# PX4FMUv2_4_6_8.net
KiCad netlist of a schematic drawn in Altium Designer
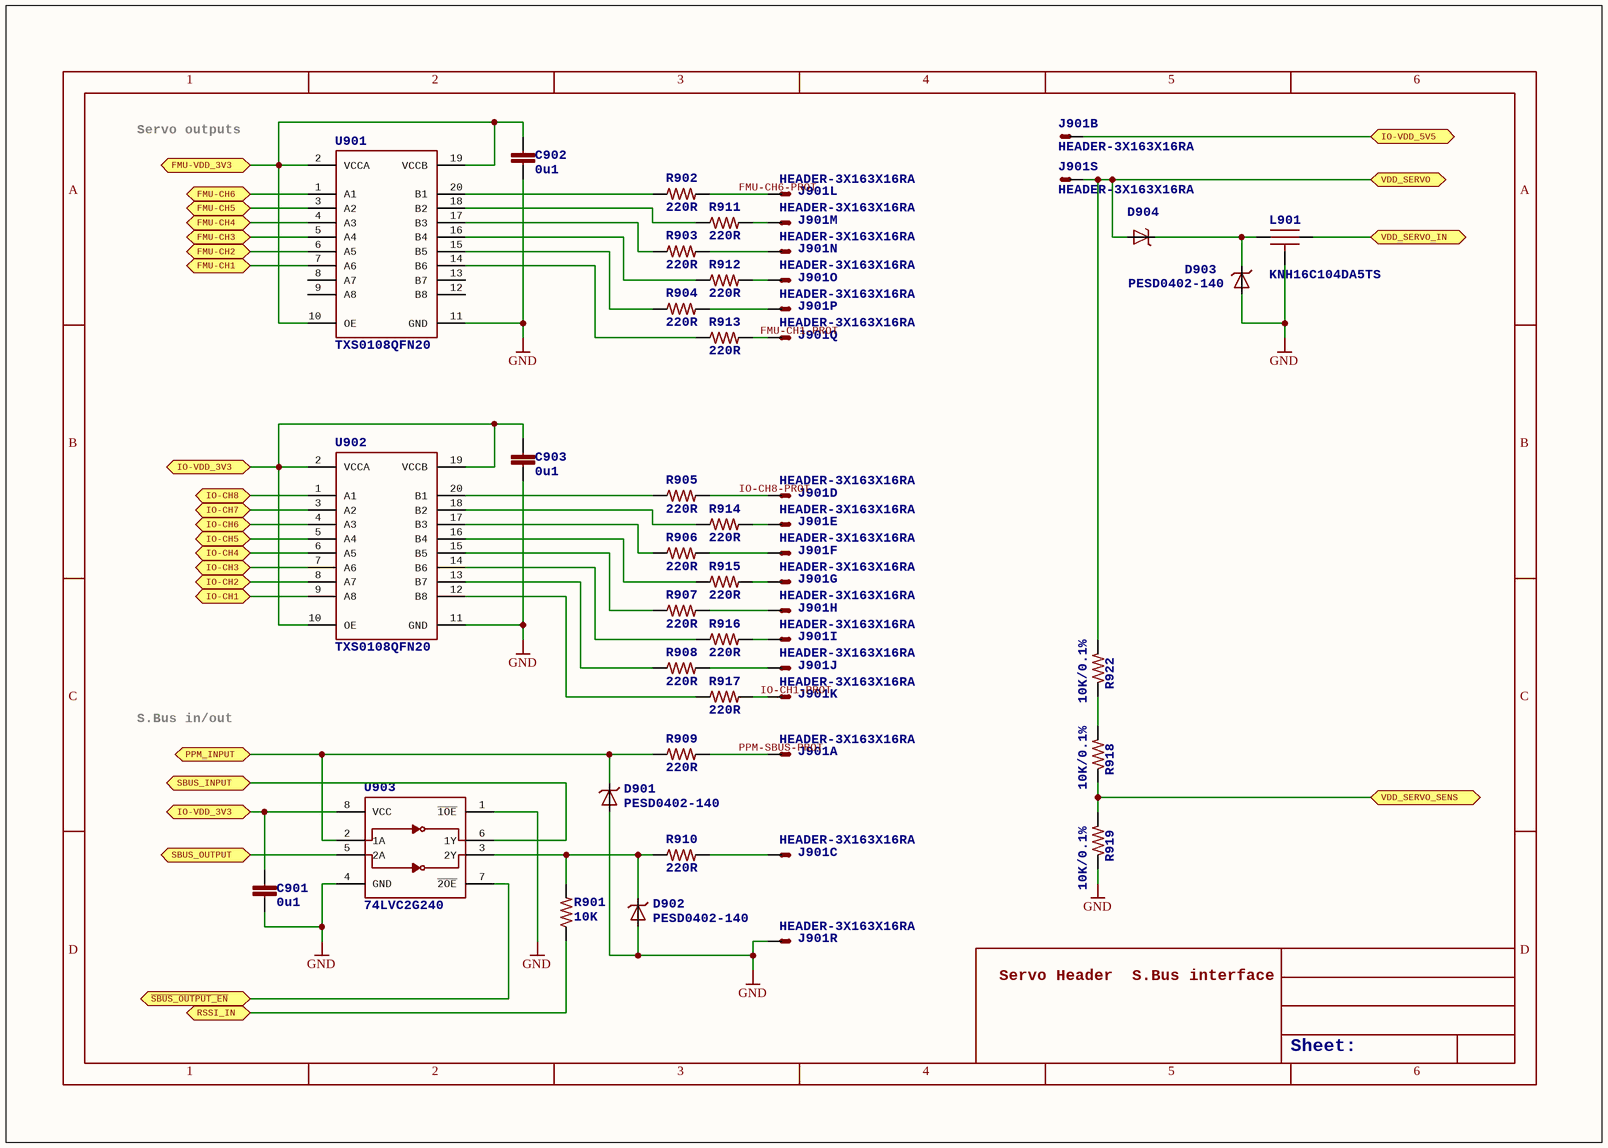
[diagram p0: PX4FMUv2.4.6_8.SchDoc]

(export (version "E")
  (design (tool "Eeschema 10.0.6"))
  (components
    (comp (ref "C901")
      (value "0u1")
      (footprint "0402-CAP")
      (description "CapacitorStandard 0603 ceramic capacitor, and 0.1\" leaded capacitor.")
      (fields (field (name "PARTNO") "CC0402ZRY5V7BB104"))
      (libsource (lib "") (part "CAP0402_1"))
    )
    (comp (ref "C902")
      (value "0u1")
      (footprint "0402-CAP")
      (description "CapacitorStandard 0603 ceramic capacitor, and 0.1\" leaded capacitor.")
      (fields (field (name "PARTNO") "CC0402ZRY5V7BB104"))
      (libsource (lib "pixhawk2") (part "CAP0402"))
    )
    (comp (ref "C903")
      (value "0u1")
      (footprint "0402-CAP")
      (description "CapacitorStandard 0603 ceramic capacitor, and 0.1\" leaded capacitor.")
      (fields (field (name "PARTNO") "CC0402ZRY5V7BB104"))
      (libsource (lib "pixhawk2") (part "CAP0402"))
    )
    (comp (ref "D901")
      (value "PESD0402-140")
      (footprint "0402-TVS")
      (libsource (lib "pixhawk2") (part "DIODE-TVS"))
    )
    (comp (ref "D902")
      (value "PESD0402-140")
      (footprint "0402-TVS")
      (libsource (lib "pixhawk2") (part "DIODE-TVS"))
    )
    (comp (ref "D903")
      (value "PESD0402-140")
      (footprint "0402-TVS")
      (libsource (lib "pixhawk2") (part "DIODE-TVS"))
    )
    (comp (ref "D904")
      (value "MSS1P4-M3")
      (footprint "MICROSMP")
      (description "Schottky barrier diode in DO214AC, e.g. Fairchild SS14.")
      (libsource (lib "pixhawk2") (part "DIODE-SCHOTTKY_MSMP"))
    )
    (comp (ref "J901")
      (value "HEADER-3X163X16RA")
      (footprint "3X16RA")
      (description "3x16 servo header")
      (libsource (lib "pixhawk2") (part "HEADER-3X163X16RA"))
    )
    (comp (ref "L901")
      (value "KNH16C104DA5TS")
      (footprint "KYOCERA-KNH16-DA")
      (description "Kyocera KNH16C104DA5TS EMI filter")
      (libsource (lib "pixhawk2") (part "KNH16C104DA5TS"))
    )
    (comp (ref "R901")
      (value "10K")
      (footprint "0402-RES")
      (fields (field (name "PARTNO") "RC0402FR-0710KL"))
      (libsource (lib "pixhawk2") (part "RESISTOR0402-RES"))
    )
    (comp (ref "R902")
      (value "220R")
      (footprint "0402-RES")
      (fields (field (name "PARTNO") "RC0402FR-07220RL"))
      (libsource (lib "pixhawk2") (part "RESISTOR0402-RES"))
    )
    (comp (ref "R903")
      (value "220R")
      (footprint "0402-RES")
      (fields (field (name "PARTNO") "RC0402FR-07220RL"))
      (libsource (lib "pixhawk2") (part "RESISTOR0402-RES"))
    )
    (comp (ref "R904")
      (value "220R")
      (footprint "0402-RES")
      (fields (field (name "PARTNO") "RC0402FR-07220RL"))
      (libsource (lib "pixhawk2") (part "RESISTOR0402-RES"))
    )
    (comp (ref "R905")
      (value "220R")
      (footprint "0402-RES")
      (fields (field (name "PARTNO") "RC0402FR-07220RL"))
      (libsource (lib "pixhawk2") (part "RESISTOR0402-RES"))
    )
    (comp (ref "R906")
      (value "220R")
      (footprint "0402-RES")
      (fields (field (name "PARTNO") "RC0402FR-07220RL"))
      (libsource (lib "pixhawk2") (part "RESISTOR0402-RES"))
    )
    (comp (ref "R907")
      (value "220R")
      (footprint "0402-RES")
      (fields (field (name "PARTNO") "RC0402FR-07220RL"))
      (libsource (lib "pixhawk2") (part "RESISTOR0402-RES"))
    )
    (comp (ref "R908")
      (value "220R")
      (footprint "0402-RES")
      (fields (field (name "PARTNO") "RC0402FR-07220RL"))
      (libsource (lib "pixhawk2") (part "RESISTOR0402-RES"))
    )
    (comp (ref "R909")
      (value "220R")
      (footprint "0402-RES")
      (fields (field (name "PARTNO") "RC0402FR-07220RL"))
      (libsource (lib "pixhawk2") (part "RESISTOR0402-RES"))
    )
    (comp (ref "R910")
      (value "220R")
      (footprint "0402-RES")
      (fields (field (name "PARTNO") "RC0402FR-07220RL"))
      (libsource (lib "pixhawk2") (part "RESISTOR0402-RES"))
    )
    (comp (ref "R911")
      (value "220R")
      (footprint "0402-RES")
      (fields (field (name "PARTNO") "RC0402FR-07220RL"))
      (libsource (lib "pixhawk2") (part "RESISTOR0402-RES"))
    )
    (comp (ref "R912")
      (value "220R")
      (footprint "0402-RES")
      (fields (field (name "PARTNO") "RC0402FR-07220RL"))
      (libsource (lib "pixhawk2") (part "RESISTOR0402-RES"))
    )
    (comp (ref "R913")
      (value "220R")
      (footprint "0402-RES")
      (fields (field (name "PARTNO") "RC0402FR-07220RL"))
      (libsource (lib "pixhawk2") (part "RESISTOR0402-RES"))
    )
    (comp (ref "R914")
      (value "220R")
      (footprint "0402-RES")
      (fields (field (name "PARTNO") "RC0402FR-07220RL"))
      (libsource (lib "pixhawk2") (part "RESISTOR0402-RES"))
    )
    (comp (ref "R915")
      (value "220R")
      (footprint "0402-RES")
      (fields (field (name "PARTNO") "RC0402FR-07220RL"))
      (libsource (lib "pixhawk2") (part "RESISTOR0402-RES"))
    )
    (comp (ref "R916")
      (value "220R")
      (footprint "0402-RES")
      (fields (field (name "PARTNO") "RC0402FR-07220RL"))
      (libsource (lib "pixhawk2") (part "RESISTOR0402-RES"))
    )
    (comp (ref "R917")
      (value "220R")
      (footprint "0402-RES")
      (fields (field (name "PARTNO") "RC0402FR-07220RL"))
      (libsource (lib "pixhawk2") (part "RESISTOR0402-RES"))
    )
    (comp (ref "R918")
      (value "10K/0.1%")
      (footprint "0402-RES")
      (libsource (lib "pixhawk2") (part "RESISTOR0402-RES"))
    )
    (comp (ref "R919")
      (value "10K/0.1%")
      (footprint "0402-RES")
      (libsource (lib "pixhawk2") (part "RESISTOR0402-RES"))
    )
    (comp (ref "R922")
      (value "10K/0.1%")
      (footprint "0402-RES")
      (libsource (lib "pixhawk2") (part "RESISTOR0402-RES"))
    )
    (comp (ref "U901")
      (value "TXS0108QFN20")
      (footprint "QFN20-RGY")
      (fields (field (name "PARTNO") "TXS0108ERGYR"))
      (libsource (lib "pixhawk2") (part "TXS0108QFN20"))
    )
    (comp (ref "U902")
      (value "TXS0108QFN20")
      (footprint "QFN20-RGY")
      (fields (field (name "PARTNO") "TXS0108ERGYR"))
      (libsource (lib "pixhawk2") (part "TXS0108QFN20"))
    )
    (comp (ref "U903")
      (value "74LVC2G240")
      (footprint "TSSOP8_SOT505-2")
      (fields (field (name "PARTNO") "74LVC2G240DP,125"))
      (libsource (lib "pixhawk2") (part "74LVC2G240-TSSOP-8"))
    )
  )
  (nets
    (net (code "1") (name "/FMU-CH1") (class "Default")
      (node (ref "U901") (pin "7") (pinfunction "A6_7") (pintype "passive"))
    )
    (net (code "2") (name "/FMU-CH1-PROT") (class "Default")
      (node (ref "J901") (pin "46") (pinfunction "S_46") (pintype "passive"))
      (node (ref "R913") (pin "P$2") (pinfunction "2_P$2") (pintype "passive"))
    )
    (net (code "3") (name "/FMU-CH2") (class "Default")
      (node (ref "U901") (pin "6") (pinfunction "A5_6") (pintype "passive"))
    )
    (net (code "4") (name "/FMU-CH3") (class "Default")
      (node (ref "U901") (pin "5") (pinfunction "A4_5") (pintype "passive"))
    )
    (net (code "5") (name "/FMU-CH4") (class "Default")
      (node (ref "U901") (pin "4") (pinfunction "A3_4") (pintype "passive"))
    )
    (net (code "6") (name "/FMU-CH5") (class "Default")
      (node (ref "U901") (pin "3") (pinfunction "A2_3") (pintype "passive"))
    )
    (net (code "7") (name "/FMU-CH6") (class "Default")
      (node (ref "U901") (pin "1") (pinfunction "A1_1") (pintype "passive"))
    )
    (net (code "8") (name "/FMU-CH6-PROT") (class "Default")
      (node (ref "J901") (pin "31") (pinfunction "S_31") (pintype "passive"))
      (node (ref "R902") (pin "P$2") (pinfunction "2_P$2") (pintype "passive"))
    )
    (net (code "9") (name "/FMU-VDD_3V3") (class "Default")
      (node (ref "C902") (pin "P$1") (pinfunction "1_P$1") (pintype "passive"))
      (node (ref "U901") (pin "10") (pinfunction "OE_10") (pintype "passive"))
      (node (ref "U901") (pin "19") (pinfunction "VCCB_19") (pintype "passive"))
      (node (ref "U901") (pin "2") (pinfunction "VCCA_2") (pintype "passive"))
    )
    (net (code "10") (name "/IO-CH1") (class "Default")
      (node (ref "U902") (pin "9") (pinfunction "A8_9") (pintype "passive"))
    )
    (net (code "11") (name "/IO-CH1-PROT") (class "Default")
      (node (ref "J901") (pin "28") (pinfunction "S_28") (pintype "passive"))
      (node (ref "R917") (pin "P$2") (pinfunction "2_P$2") (pintype "passive"))
    )
    (net (code "12") (name "/IO-CH2") (class "Default")
      (node (ref "U902") (pin "8") (pinfunction "A7_8") (pintype "passive"))
    )
    (net (code "13") (name "/IO-CH3") (class "Default")
      (node (ref "U902") (pin "7") (pinfunction "A6_7") (pintype "passive"))
    )
    (net (code "14") (name "/IO-CH4") (class "Default")
      (node (ref "U902") (pin "6") (pinfunction "A5_6") (pintype "passive"))
    )
    (net (code "15") (name "/IO-CH5") (class "Default")
      (node (ref "U902") (pin "5") (pinfunction "A4_5") (pintype "passive"))
    )
    (net (code "16") (name "/IO-CH6") (class "Default")
      (node (ref "U902") (pin "4") (pinfunction "A3_4") (pintype "passive"))
    )
    (net (code "17") (name "/IO-CH7") (class "Default")
      (node (ref "U902") (pin "3") (pinfunction "A2_3") (pintype "passive"))
    )
    (net (code "18") (name "/IO-CH8") (class "Default")
      (node (ref "U902") (pin "1") (pinfunction "A1_1") (pintype "passive"))
    )
    (net (code "19") (name "/IO-CH8-PROT") (class "Default")
      (node (ref "J901") (pin "7") (pinfunction "S_7") (pintype "passive"))
      (node (ref "R905") (pin "P$2") (pinfunction "2_P$2") (pintype "passive"))
    )
    (net (code "20") (name "/IO-VDD_3V3") (class "Default")
      (node (ref "C901") (pin "P$1") (pinfunction "1_P$1") (pintype "passive"))
      (node (ref "C903") (pin "P$1") (pinfunction "1_P$1") (pintype "passive"))
      (node (ref "U902") (pin "10") (pinfunction "OE_10") (pintype "passive"))
      (node (ref "U902") (pin "19") (pinfunction "VCCB_19") (pintype "passive"))
      (node (ref "U902") (pin "2") (pinfunction "VCCA_2") (pintype "passive"))
      (node (ref "U903") (pin "8") (pinfunction "VCC_8") (pintype "open_emitter"))
    )
    (net (code "21") (name "/IO-VDD_5V5") (class "Default")
      (node (ref "J901") (pin "2") (pinfunction "S_2") (pintype "passive"))
    )
    (net (code "22") (name "/PPM-SBUS-PROT") (class "Default")
      (node (ref "J901") (pin "1") (pinfunction "S_1") (pintype "passive"))
      (node (ref "R909") (pin "P$2") (pinfunction "2_P$2") (pintype "passive"))
    )
    (net (code "23") (name "/PPM_INPUT") (class "Default")
      (node (ref "D901") (pin "C") (pinfunction "C_C") (pintype "passive"))
      (node (ref "R909") (pin "P$1") (pinfunction "1_P$1") (pintype "passive"))
      (node (ref "U903") (pin "2") (pinfunction "1A_2") (pintype "passive"))
    )
    (net (code "24") (name "/RSSI_IN") (class "Default")
      (node (ref "R901") (pin "P$1") (pinfunction "1_P$1") (pintype "passive"))
    )
    (net (code "25") (name "/SBUS_INPUT") (class "Default")
      (node (ref "U903") (pin "6") (pinfunction "1Y_6") (pintype "passive"))
    )
    (net (code "26") (name "/SBUS_OUTPUT") (class "Default")
      (node (ref "U903") (pin "5") (pinfunction "2A_5") (pintype "passive"))
    )
    (net (code "27") (name "/VDD_SERVO") (class "Default")
      (node (ref "D904") (pin "ANODE") (pinfunction "A_ANODE") (pintype "passive"))
      (node (ref "J901") (pin "5_8_11_14_17_20_23_26_29_32_35_38_41_44_47") (pinfunction "S_5_8_11_14_17_20_23_26_29_32_35_38_41_44_47") (pintype "passive"))
      (node (ref "R922") (pin "P$2") (pinfunction "2_P$2") (pintype "passive"))
    )
    (net (code "28") (name "/VDD_SERVO_IN") (class "Default")
      (node (ref "L901") (pin "P$2") (pinfunction "P$2_P$2") (pintype "passive"))
    )
    (net (code "29") (name "/VDD_SERVO_SENS") (class "Default")
      (node (ref "R918") (pin "P$1") (pinfunction "1_P$1") (pintype "passive"))
      (node (ref "R919") (pin "P$2") (pinfunction "2_P$2") (pintype "passive"))
    )
    (net (code "30") (name "/~{SBUS_OUTPUT_EN}") (class "Default")
      (node (ref "U903") (pin "7") (pinfunction "~{2OE}_7") (pintype "passive"))
    )
    (net (code "31") (name "GND") (class "Default")
      (node (ref "C901") (pin "P$2") (pinfunction "2_P$2") (pintype "passive"))
      (node (ref "C902") (pin "P$2") (pinfunction "2_P$2") (pintype "passive"))
      (node (ref "C903") (pin "P$2") (pinfunction "2_P$2") (pintype "passive"))
      (node (ref "D901") (pin "A") (pinfunction "A_A") (pintype "passive"))
      (node (ref "D902") (pin "A") (pinfunction "A_A") (pintype "passive"))
      (node (ref "D903") (pin "A") (pinfunction "A_A") (pintype "passive"))
      (node (ref "J901") (pin "3_6_9_12_15_18_21_24_27_30_33_36_39_42_45_48") (pinfunction "S_3_6_9_12_15_18_21_24_27_30_33_36_39_42_45_48") (pintype "passive"))
      (node (ref "L901") (pin "P$3_P$4_P$5") (pinfunction "P$3_P$3_P$4_P$5") (pintype "passive"))
      (node (ref "R919") (pin "P$1") (pinfunction "1_P$1") (pintype "passive"))
      (node (ref "U901") (pin "11") (pinfunction "GND_11") (pintype "open_emitter"))
      (node (ref "U902") (pin "11") (pinfunction "GND_11") (pintype "open_emitter"))
      (node (ref "U903") (pin "1") (pinfunction "~{1OE}_1") (pintype "passive"))
      (node (ref "U903") (pin "4") (pinfunction "GND_4") (pintype "open_emitter"))
    )
    (net (code "32") (name "Net-(D904-C)") (class "Default")
      (node (ref "D903") (pin "C") (pinfunction "C_C") (pintype "passive"))
      (node (ref "D904") (pin "CATHODE") (pinfunction "C_CATHODE") (pintype "passive"))
      (node (ref "L901") (pin "P$1") (pinfunction "P$1_P$1") (pintype "passive"))
    )
    (net (code "33") (name "Net-(J901C-S)") (class "Default")
      (node (ref "J901") (pin "4") (pinfunction "S_4") (pintype "passive"))
      (node (ref "R910") (pin "P$2") (pinfunction "2_P$2") (pintype "passive"))
    )
    (net (code "34") (name "Net-(J901E-S)") (class "Default")
      (node (ref "J901") (pin "10") (pinfunction "S_10") (pintype "passive"))
      (node (ref "R914") (pin "P$2") (pinfunction "2_P$2") (pintype "passive"))
    )
    (net (code "35") (name "Net-(J901F-S)") (class "Default")
      (node (ref "J901") (pin "13") (pinfunction "S_13") (pintype "passive"))
      (node (ref "R906") (pin "P$2") (pinfunction "2_P$2") (pintype "passive"))
    )
    (net (code "36") (name "Net-(J901G-S)") (class "Default")
      (node (ref "J901") (pin "16") (pinfunction "S_16") (pintype "passive"))
      (node (ref "R915") (pin "P$2") (pinfunction "2_P$2") (pintype "passive"))
    )
    (net (code "37") (name "Net-(J901H-S)") (class "Default")
      (node (ref "J901") (pin "19") (pinfunction "S_19") (pintype "passive"))
      (node (ref "R907") (pin "P$2") (pinfunction "2_P$2") (pintype "passive"))
    )
    (net (code "38") (name "Net-(J901I-S)") (class "Default")
      (node (ref "J901") (pin "22") (pinfunction "S_22") (pintype "passive"))
      (node (ref "R916") (pin "P$2") (pinfunction "2_P$2") (pintype "passive"))
    )
    (net (code "39") (name "Net-(J901J-S)") (class "Default")
      (node (ref "J901") (pin "25") (pinfunction "S_25") (pintype "passive"))
      (node (ref "R908") (pin "P$2") (pinfunction "2_P$2") (pintype "passive"))
    )
    (net (code "40") (name "Net-(J901M-S)") (class "Default")
      (node (ref "J901") (pin "34") (pinfunction "S_34") (pintype "passive"))
      (node (ref "R911") (pin "P$2") (pinfunction "2_P$2") (pintype "passive"))
    )
    (net (code "41") (name "Net-(J901N-S)") (class "Default")
      (node (ref "J901") (pin "37") (pinfunction "S_37") (pintype "passive"))
      (node (ref "R903") (pin "P$2") (pinfunction "2_P$2") (pintype "passive"))
    )
    (net (code "42") (name "Net-(J901O-S)") (class "Default")
      (node (ref "J901") (pin "40") (pinfunction "S_40") (pintype "passive"))
      (node (ref "R912") (pin "P$2") (pinfunction "2_P$2") (pintype "passive"))
    )
    (net (code "43") (name "Net-(J901P-S)") (class "Default")
      (node (ref "J901") (pin "43") (pinfunction "S_43") (pintype "passive"))
      (node (ref "R904") (pin "P$2") (pinfunction "2_P$2") (pintype "passive"))
    )
    (net (code "44") (name "Net-(R901-2)") (class "Default")
      (node (ref "D902") (pin "C") (pinfunction "C_C") (pintype "passive"))
      (node (ref "R901") (pin "P$2") (pinfunction "2_P$2") (pintype "passive"))
      (node (ref "R910") (pin "P$1") (pinfunction "1_P$1") (pintype "passive"))
      (node (ref "U903") (pin "3") (pinfunction "2Y_3") (pintype "passive"))
    )
    (net (code "45") (name "Net-(R902-1)") (class "Default")
      (node (ref "R902") (pin "P$1") (pinfunction "1_P$1") (pintype "passive"))
      (node (ref "U901") (pin "20") (pinfunction "B1_20") (pintype "passive"))
    )
    (net (code "46") (name "Net-(R903-1)") (class "Default")
      (node (ref "R903") (pin "P$1") (pinfunction "1_P$1") (pintype "passive"))
      (node (ref "U901") (pin "17") (pinfunction "B3_17") (pintype "passive"))
    )
    (net (code "47") (name "Net-(R904-1)") (class "Default")
      (node (ref "R904") (pin "P$1") (pinfunction "1_P$1") (pintype "passive"))
      (node (ref "U901") (pin "15") (pinfunction "B5_15") (pintype "passive"))
    )
    (net (code "48") (name "Net-(R905-1)") (class "Default")
      (node (ref "R905") (pin "P$1") (pinfunction "1_P$1") (pintype "passive"))
      (node (ref "U902") (pin "20") (pinfunction "B1_20") (pintype "passive"))
    )
    (net (code "49") (name "Net-(R906-1)") (class "Default")
      (node (ref "R906") (pin "P$1") (pinfunction "1_P$1") (pintype "passive"))
      (node (ref "U902") (pin "17") (pinfunction "B3_17") (pintype "passive"))
    )
    (net (code "50") (name "Net-(R907-1)") (class "Default")
      (node (ref "R907") (pin "P$1") (pinfunction "1_P$1") (pintype "passive"))
      (node (ref "U902") (pin "15") (pinfunction "B5_15") (pintype "passive"))
    )
    (net (code "51") (name "Net-(R908-1)") (class "Default")
      (node (ref "R908") (pin "P$1") (pinfunction "1_P$1") (pintype "passive"))
      (node (ref "U902") (pin "13") (pinfunction "B7_13") (pintype "passive"))
    )
    (net (code "52") (name "Net-(R911-1)") (class "Default")
      (node (ref "R911") (pin "P$1") (pinfunction "1_P$1") (pintype "passive"))
      (node (ref "U901") (pin "18") (pinfunction "B2_18") (pintype "passive"))
    )
    (net (code "53") (name "Net-(R912-1)") (class "Default")
      (node (ref "R912") (pin "P$1") (pinfunction "1_P$1") (pintype "passive"))
      (node (ref "U901") (pin "16") (pinfunction "B4_16") (pintype "passive"))
    )
    (net (code "54") (name "Net-(R913-1)") (class "Default")
      (node (ref "R913") (pin "P$1") (pinfunction "1_P$1") (pintype "passive"))
      (node (ref "U901") (pin "14") (pinfunction "B6_14") (pintype "passive"))
    )
    (net (code "55") (name "Net-(R914-1)") (class "Default")
      (node (ref "R914") (pin "P$1") (pinfunction "1_P$1") (pintype "passive"))
      (node (ref "U902") (pin "18") (pinfunction "B2_18") (pintype "passive"))
    )
    (net (code "56") (name "Net-(R915-1)") (class "Default")
      (node (ref "R915") (pin "P$1") (pinfunction "1_P$1") (pintype "passive"))
      (node (ref "U902") (pin "16") (pinfunction "B4_16") (pintype "passive"))
    )
    (net (code "57") (name "Net-(R916-1)") (class "Default")
      (node (ref "R916") (pin "P$1") (pinfunction "1_P$1") (pintype "passive"))
      (node (ref "U902") (pin "14") (pinfunction "B6_14") (pintype "passive"))
    )
    (net (code "58") (name "Net-(R917-1)") (class "Default")
      (node (ref "R917") (pin "P$1") (pinfunction "1_P$1") (pintype "passive"))
      (node (ref "U902") (pin "12") (pinfunction "B8_12") (pintype "passive"))
    )
    (net (code "59") (name "Net-(R918-2)") (class "Default")
      (node (ref "R918") (pin "P$2") (pinfunction "2_P$2") (pintype "passive"))
      (node (ref "R922") (pin "P$1") (pinfunction "1_P$1") (pintype "passive"))
    )
    (net (code "60") (name "unconnected-(U901-A7-Pad8)") (class "Default")
      (node (ref "U901") (pin "8") (pinfunction "A7_8") (pintype "passive"))
    )
    (net (code "61") (name "unconnected-(U901-A8-Pad9)") (class "Default")
      (node (ref "U901") (pin "9") (pinfunction "A8_9") (pintype "passive"))
    )
    (net (code "62") (name "unconnected-(U901-B7-Pad13)") (class "Default")
      (node (ref "U901") (pin "13") (pinfunction "B7_13") (pintype "passive"))
    )
    (net (code "63") (name "unconnected-(U901-B8-Pad12)") (class "Default")
      (node (ref "U901") (pin "12") (pinfunction "B8_12") (pintype "passive"))
    )
  )
)
